# Sheet1.net
KiCad netlist of a schematic drawn in Altium Designer
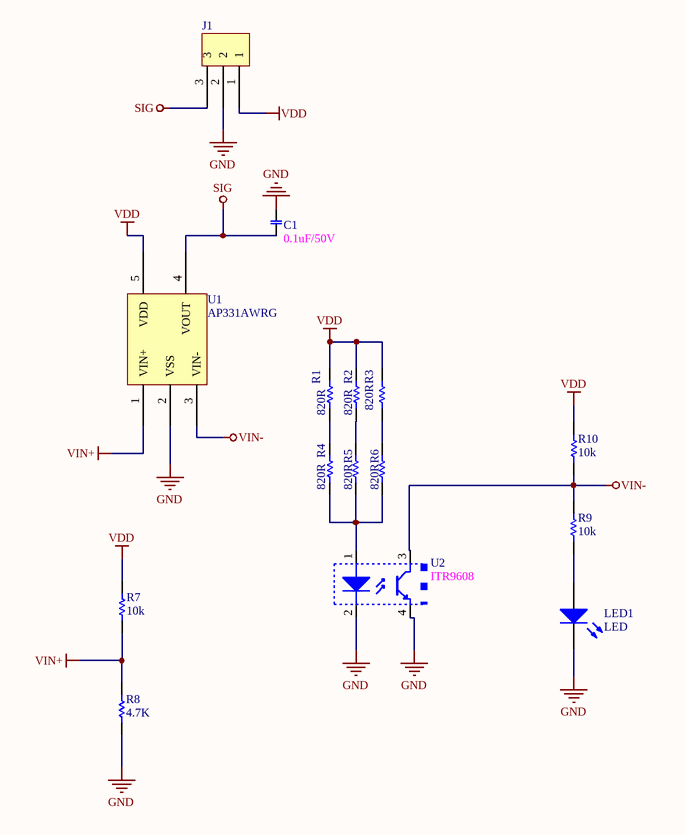
[diagram p0: Sheet1.SchDoc]

(export (version "E")
  (design (tool "Eeschema 10.0.6"))
  (components
    (comp (ref "C1")
      (value "0.1uF/50V")
      (footprint "C0603T")
      (description "CAP MC SMD 50V 22pF J C0G 0603")
      (fields (field (name "MPN") "GRM1885C1H220JA01D"))
      (libsource (lib "XY-EV-V1.1") (part "CAP"))
    )
    (comp (ref "J1") (value "3*1.27") (footprint "XH2.54-3AW") (libsource (lib "3P_1.27") (part "3PIN_1.27")))
    (comp (ref "LED1") (value "LED") (footprint "my:LED0603") (libsource (lib "清洗固化") (part "LED_1")))
    (comp (ref "R1")
      (value "820R")
      (footprint "R0805")
      (description "Resistor")
      (fields (field (name "PUBLISHER") "Altium Limited"))
      (libsource (lib "清洗固化") (part "Res1_2"))
    )
    (comp (ref "R2")
      (value "820R")
      (footprint "R0805")
      (description "Resistor")
      (fields (field (name "PUBLISHER") "Altium Limited"))
      (libsource (lib "清洗固化") (part "Res1_2"))
    )
    (comp (ref "R3")
      (value "820R")
      (footprint "R0805")
      (description "Resistor")
      (fields (field (name "PUBLISHER") "Altium Limited"))
      (libsource (lib "清洗固化") (part "Res1_2"))
    )
    (comp (ref "R4")
      (value "820R")
      (footprint "R0805")
      (description "Resistor")
      (fields (field (name "PUBLISHER") "Altium Limited"))
      (libsource (lib "清洗固化") (part "Res1_2"))
    )
    (comp (ref "R5")
      (value "820R")
      (footprint "R0805")
      (description "Resistor")
      (fields (field (name "PUBLISHER") "Altium Limited"))
      (libsource (lib "清洗固化") (part "Res1_2"))
    )
    (comp (ref "R6")
      (value "820R")
      (footprint "R0805")
      (description "Resistor")
      (fields (field (name "PUBLISHER") "Altium Limited"))
      (libsource (lib "清洗固化") (part "Res1_2"))
    )
    (comp (ref "R7")
      (value "10k")
      (footprint "R0603")
      (description "Resistor")
      (fields (field (name "PUBLISHER") "Altium Limited"))
      (libsource (lib "清洗固化") (part "Res1"))
    )
    (comp (ref "R8")
      (value "4.7K")
      (footprint "R0603")
      (description "Resistor")
      (fields (field (name "PUBLISHER") "Altium Limited"))
      (libsource (lib "清洗固化") (part "Res1"))
    )
    (comp (ref "R9")
      (value "10k")
      (footprint "R0603")
      (description "Resistor")
      (fields (field (name "PUBLISHER") "Altium Limited"))
      (libsource (lib "清洗固化") (part "Res1"))
    )
    (comp (ref "R10")
      (value "10k")
      (footprint "R0603")
      (description "Resistor")
      (fields (field (name "PUBLISHER") "Altium Limited"))
      (libsource (lib "清洗固化") (part "Res1"))
    )
    (comp (ref "U1") (value "AP331AWRG") (footprint "SOT23-5") (libsource (lib "OP") (part "OP")))
    (comp (ref "U2")
      (value "ITR9608")
      (footprint "ITR9608")
      (description "PHOTOCOUPLER PS2701A 70V 30mA L rank SMD")
      (fields (field (name "MPN") "PS2701A L rank"))
      (libsource (lib "XY-EV-V1.1") (part "PHOTO-1"))
    )
  )
  (nets
    (net (code "1") (name "GND") (class "Default")
      (node (ref "C1") (pin "2") (pintype "passive"))
      (node (ref "J1") (pin "2") (pinfunction "2_2") (pintype "passive"))
      (node (ref "LED1") (pin "2") (pinfunction "K_2") (pintype "passive"))
      (node (ref "R8") (pin "2") (pinfunction "2_2") (pintype "passive"))
      (node (ref "U1") (pin "2") (pinfunction "VSS_2") (pintype "passive"))
      (node (ref "U2") (pin "2") (pinfunction "2_2") (pintype "passive"))
      (node (ref "U2") (pin "4") (pinfunction "4_4") (pintype "passive"))
    )
    (net (code "2") (name "Net-(LED1-A)") (class "Default")
      (node (ref "LED1") (pin "1") (pinfunction "A_1") (pintype "passive"))
      (node (ref "R9") (pin "1") (pinfunction "1_1") (pintype "passive"))
    )
    (net (code "3") (name "Net-(R1-Pad1)") (class "Default")
      (node (ref "R1") (pin "1") (pinfunction "1_1") (pintype "passive"))
      (node (ref "R4") (pin "2") (pinfunction "2_2") (pintype "passive"))
    )
    (net (code "4") (name "Net-(R2-Pad1)") (class "Default")
      (node (ref "R2") (pin "1") (pinfunction "1_1") (pintype "passive"))
      (node (ref "R5") (pin "2") (pinfunction "2_2") (pintype "passive"))
    )
    (net (code "5") (name "Net-(R3-Pad1)") (class "Default")
      (node (ref "R3") (pin "1") (pinfunction "1_1") (pintype "passive"))
      (node (ref "R6") (pin "2") (pinfunction "2_2") (pintype "passive"))
    )
    (net (code "6") (name "Net-(R4-Pad1)") (class "Default")
      (node (ref "R4") (pin "1") (pinfunction "1_1") (pintype "passive"))
      (node (ref "R5") (pin "1") (pinfunction "1_1") (pintype "passive"))
      (node (ref "R6") (pin "1") (pinfunction "1_1") (pintype "passive"))
      (node (ref "U2") (pin "1") (pinfunction "1_1") (pintype "passive"))
    )
    (net (code "7") (name "SIG") (class "Default")
      (node (ref "C1") (pin "1") (pintype "passive"))
      (node (ref "J1") (pin "3") (pinfunction "3_3") (pintype "passive"))
      (node (ref "U1") (pin "4") (pinfunction "VOUT_4") (pintype "passive"))
    )
    (net (code "8") (name "VDD") (class "Default")
      (node (ref "J1") (pin "1") (pinfunction "1_1") (pintype "passive"))
      (node (ref "R1") (pin "2") (pinfunction "2_2") (pintype "passive"))
      (node (ref "R10") (pin "2") (pinfunction "2_2") (pintype "passive"))
      (node (ref "R2") (pin "2") (pinfunction "2_2") (pintype "passive"))
      (node (ref "R3") (pin "2") (pinfunction "2_2") (pintype "passive"))
      (node (ref "R7") (pin "2") (pinfunction "2_2") (pintype "passive"))
      (node (ref "U1") (pin "5") (pinfunction "VDD_5") (pintype "passive"))
    )
    (net (code "9") (name "VIN+") (class "Default")
      (node (ref "R7") (pin "1") (pinfunction "1_1") (pintype "passive"))
      (node (ref "R8") (pin "1") (pinfunction "1_1") (pintype "passive"))
      (node (ref "U1") (pin "1") (pinfunction "VIN+_1") (pintype "passive"))
    )
    (net (code "10") (name "VIN-") (class "Default")
      (node (ref "R10") (pin "1") (pinfunction "1_1") (pintype "passive"))
      (node (ref "R9") (pin "2") (pinfunction "2_2") (pintype "passive"))
      (node (ref "U1") (pin "3") (pinfunction "VIN-_3") (pintype "passive"))
      (node (ref "U2") (pin "3") (pinfunction "3_3") (pintype "passive"))
    )
  )
)
